# M30517_TX_V1_0.net
KiCad netlist of a schematic drawn in Altium Designer
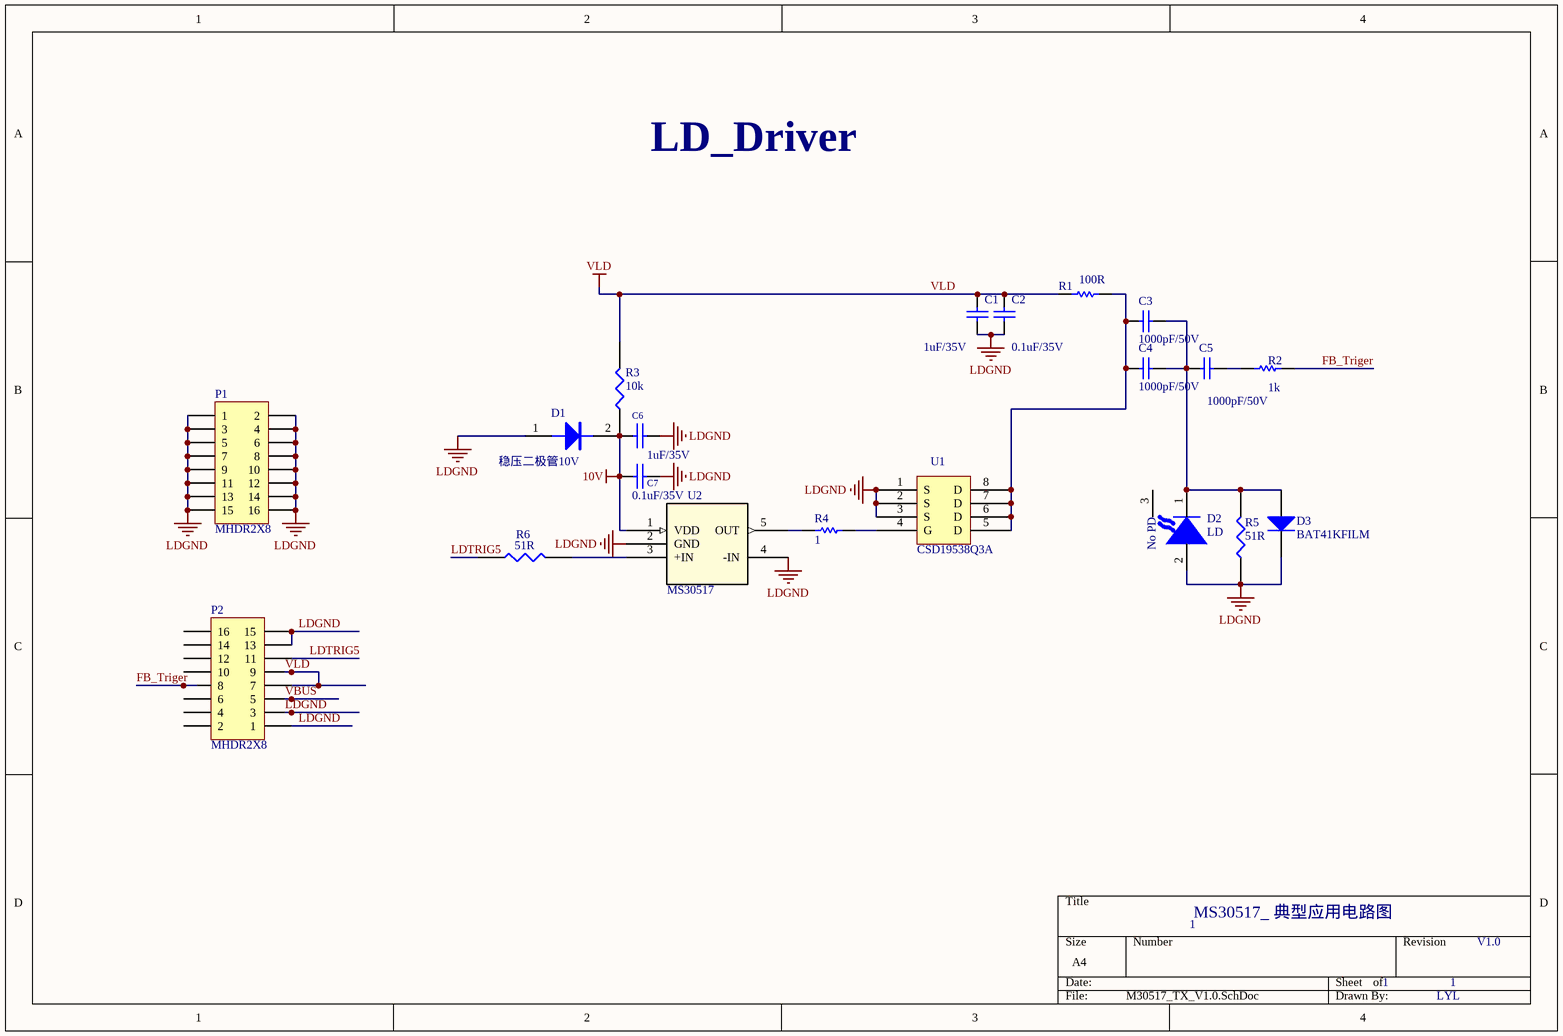
[diagram p0: M30517_TX_V1.0.SchDoc]

(export (version "E")
  (design (tool "Eeschema 10.0.6"))
  (components
    (comp (ref "C1")
      (value "1uF/35V")
      (footprint "C 0603_L")
      (description "Walsin - 1uF, 50V, X5R, 10%")
      (fields (field (name "Comment") "0603X105K500CT") (field (name "PUBLISHER") "Altium Limited"))
      (libsource (lib "Miscellaneous Devices") (part "Cap"))
    )
    (comp (ref "C2")
      (value "0.1uF/35V")
      (footprint "C 0603_L")
      (description "Walsin - 1uF, 50V, X5R, 10%")
      (fields (field (name "Comment") "0603X105K500CT") (field (name "PUBLISHER") "Altium Limited"))
      (libsource (lib "Miscellaneous Devices") (part "Cap"))
    )
    (comp (ref "C3")
      (value "1000pF/50V")
      (footprint "C 0603_L")
      (description "1000pF,  0402 ,50V, NP0, 2%")
      (fields (field (name "Comment") "C0402C331J1GACAUTO") (field (name "PUBLISHER") "Altium Limited"))
      (libsource (lib "Miscellaneous Devices") (part "Cap"))
    )
    (comp (ref "C4")
      (value "1000pF/50V")
      (footprint "C 0603_L")
      (description "1000pF,  0402 ,50V, NP0, 5%")
      (fields (field (name "PUBLISHER") "Altium Limited"))
      (libsource (lib "Miscellaneous Devices") (part "Cap"))
    )
    (comp (ref "C5")
      (value "1000pF/50V")
      (footprint "C 0603_L")
      (description "1000pF,  0402 ,50V, NP0, 2%")
      (fields (field (name "PUBLISHER") "Altium Limited"))
      (libsource (lib "Miscellaneous Devices") (part "Cap"))
    )
    (comp (ref "C6")
      (value "1uF/35V")
      (footprint "C 0603_L")
      (description "Murata - 1nF, 50V, X7R, 10%")
      (fields (field (name "Comment") "GRM155R71H102KA01D"))
      (libsource (lib "*") (part "CAP"))
    )
    (comp (ref "C7")
      (value "0.1uF/35V")
      (footprint "C 0603_L")
      (description "Murata - 0.1uF, 50V, X7R, 10%")
      (fields (field (name "Comment") "(*)GCM155R71H104KE02D"))
      (libsource (lib "*") (part "CAP"))
    )
    (comp (ref "D1")
      (value "稳压二极管10V")
      (footprint "SOD-323")
      (description "Diode")
      (libsource (lib "*") (part "DIODE"))
    )
    (comp (ref "D2")
      (value "LD")
      (footprint "LD1")
      (description "Laser")
      (libsource (lib "Myschpassive") (part "LD_Cathode_NOPD"))
    )
    (comp (ref "D3")
      (value "BAT41KFILM")
      (footprint "SOD-523")
      (description "STM - Sckottky, 200mA, 100 V")
      (fields (field (name "PUBLISHER") "Altium Limited"))
      (libsource (lib "Miscellaneous Devices") (part "Diode"))
    )
    (comp (ref "P1")
      (value "MHDR2X8")
      (footprint "HDR2.54-M-LS-2x8P")
      (description "Header, 8-Pin, Dual row")
      (fields (field (name "PUBLISHER") "Altium Limited"))
      (libsource (lib "Miscellaneous Connectors") (part "MHDR2X8"))
    )
    (comp (ref "P2")
      (value "MHDR2X8")
      (footprint "HDR2.54-M-LS-2x8P")
      (description "Header, 8-Pin, Dual row")
      (fields (field (name "PUBLISHER") "Altium Limited"))
      (libsource (lib "") (part "MHDR2X8_1"))
    )
    (comp (ref "R1")
      (value "100R")
      (footprint "0603R")
      (description "Yageo - 1K, 1/8W, 1 %")
      (fields (field (name "PUBLISHER") "Altium Limited"))
      (libsource (lib "Miscellaneous Devices") (part "Res1"))
    )
    (comp (ref "R2")
      (value "1k")
      (footprint "0603R")
      (description "Yageo - 1K, 1/8W, 1 %")
      (fields (field (name "Comment") "RC0402FR-7W1KL") (field (name "PUBLISHER") "Altium Limited"))
      (libsource (lib "Miscellaneous Devices") (part "Res1"))
    )
    (comp (ref "R3") (value "10k") (footprint "0603R") (libsource (lib "*") (part "RES1")))
    (comp (ref "R4")
      (value "1")
      (footprint "0603R")
      (description "10ohm, 0402,1/16W, 1 %")
      (fields (field (name "Comment") "CR0402F10RQ10") (field (name "PUBLISHER") "Altium Limited"))
      (libsource (lib "Miscellaneous Devices") (part "Res1"))
    )
    (comp (ref "R5") (value "51R") (footprint "0603R") (libsource (lib "*") (part "RES1")))
    (comp (ref "R6") (value "51R") (footprint "0603R") (libsource (lib "*") (part "RES1")))
    (comp (ref "U1") (value "CSD19538Q3A") (footprint "QA3") (libsource (lib "Schlib2") (part "N_MOSFET")))
    (comp (ref "U2")
      (value "MS30517")
      (footprint "SOT23-5")
      (description "UCC27157")
      (fields
        (field (name "MANUFACTURER_PART_NUMBER") "MCP9501PT-115E/OT")
        (field (name "COPYRIGHT") "Copyright (C) 2018 Accelerated Designs. All rights reserved")
      )
      (libsource (lib "schlib") (part "UC27517A"))
    )
  )
  (nets
    (net (code "1") (name "/FB_Triger") (class "Default")
      (node (ref "P2") (pin "8") (pinfunction "8_8") (pintype "passive"))
      (node (ref "R2") (pin "1") (pinfunction "1_1") (pintype "passive"))
    )
    (net (code "2") (name "/LDTRIG5") (class "Default")
      (node (ref "P2") (pin "11") (pinfunction "11_11") (pintype "passive"))
      (node (ref "R6") (pin "1") (pinfunction "1_1") (pintype "passive"))
    )
    (net (code "3") (name "/VBUS") (class "Default")
      (node (ref "P2") (pin "5") (pinfunction "5_5") (pintype "passive"))
    )
    (net (code "4") (name "10V") (class "Default")
      (node (ref "C6") (pin "2") (pinfunction "2_2") (pintype "passive"))
      (node (ref "C7") (pin "2") (pinfunction "2_2") (pintype "passive"))
      (node (ref "D1") (pin "2") (pinfunction "K_2") (pintype "passive"))
      (node (ref "R3") (pin "1") (pinfunction "1_1") (pintype "passive"))
      (node (ref "U2") (pin "1") (pinfunction "VDD_1") (pintype "input"))
    )
    (net (code "5") (name "LDGND") (class "Default")
      (node (ref "C1") (pin "2") (pinfunction "2_2") (pintype "passive"))
      (node (ref "C2") (pin "2") (pinfunction "2_2") (pintype "passive"))
      (node (ref "C6") (pin "1") (pinfunction "1_1") (pintype "passive"))
      (node (ref "C7") (pin "1") (pinfunction "1_1") (pintype "passive"))
      (node (ref "D1") (pin "1") (pinfunction "A_1") (pintype "passive"))
      (node (ref "D2") (pin "2") (pintype "passive"))
      (node (ref "D3") (pin "2") (pinfunction "K_2") (pintype "passive"))
      (node (ref "P1") (pin "1") (pinfunction "1_1") (pintype "passive"))
      (node (ref "P1") (pin "10") (pinfunction "10_10") (pintype "passive"))
      (node (ref "P1") (pin "11") (pinfunction "11_11") (pintype "passive"))
      (node (ref "P1") (pin "12") (pinfunction "12_12") (pintype "passive"))
      (node (ref "P1") (pin "13") (pinfunction "13_13") (pintype "passive"))
      (node (ref "P1") (pin "14") (pinfunction "14_14") (pintype "passive"))
      (node (ref "P1") (pin "15") (pinfunction "15_15") (pintype "passive"))
      (node (ref "P1") (pin "16") (pinfunction "16_16") (pintype "passive"))
      (node (ref "P1") (pin "2") (pinfunction "2_2") (pintype "passive"))
      (node (ref "P1") (pin "3") (pinfunction "3_3") (pintype "passive"))
      (node (ref "P1") (pin "4") (pinfunction "4_4") (pintype "passive"))
      (node (ref "P1") (pin "5") (pinfunction "5_5") (pintype "passive"))
      (node (ref "P1") (pin "6") (pinfunction "6_6") (pintype "passive"))
      (node (ref "P1") (pin "7") (pinfunction "7_7") (pintype "passive"))
      (node (ref "P1") (pin "8") (pinfunction "8_8") (pintype "passive"))
      (node (ref "P1") (pin "9") (pinfunction "9_9") (pintype "passive"))
      (node (ref "P2") (pin "1") (pinfunction "1_1") (pintype "passive"))
      (node (ref "P2") (pin "13") (pinfunction "13_13") (pintype "passive"))
      (node (ref "P2") (pin "15") (pinfunction "15_15") (pintype "passive"))
      (node (ref "P2") (pin "3") (pinfunction "3_3") (pintype "passive"))
      (node (ref "R5") (pin "1") (pinfunction "1_1") (pintype "passive"))
      (node (ref "U1") (pin "1") (pinfunction "S_1") (pintype "passive"))
      (node (ref "U1") (pin "2") (pinfunction "S_2") (pintype "passive"))
      (node (ref "U1") (pin "3") (pinfunction "S_3") (pintype "passive"))
      (node (ref "U2") (pin "2") (pinfunction "GND_2") (pintype "power_in"))
      (node (ref "U2") (pin "4") (pinfunction "-IN_4") (pintype "power_in"))
    )
    (net (code "6") (name "Net-(C3-Pad1)") (class "Default")
      (node (ref "C3") (pin "1") (pinfunction "1_1") (pintype "passive"))
      (node (ref "C4") (pin "1") (pinfunction "1_1") (pintype "passive"))
      (node (ref "R1") (pin "1") (pinfunction "1_1") (pintype "passive"))
      (node (ref "U1") (pin "5") (pinfunction "D_5") (pintype "passive"))
      (node (ref "U1") (pin "6") (pinfunction "D_6") (pintype "passive"))
      (node (ref "U1") (pin "7") (pinfunction "D_7") (pintype "passive"))
      (node (ref "U1") (pin "8") (pinfunction "D_8") (pintype "passive"))
    )
    (net (code "7") (name "Net-(C5-Pad2)") (class "Default")
      (node (ref "C5") (pin "2") (pinfunction "2_2") (pintype "passive"))
      (node (ref "R2") (pin "2") (pinfunction "2_2") (pintype "passive"))
    )
    (net (code "8") (name "Net-(D3-A)") (class "Default")
      (node (ref "C3") (pin "2") (pinfunction "2_2") (pintype "passive"))
      (node (ref "C4") (pin "2") (pinfunction "2_2") (pintype "passive"))
      (node (ref "C5") (pin "1") (pinfunction "1_1") (pintype "passive"))
      (node (ref "D2") (pin "1") (pintype "passive"))
      (node (ref "D3") (pin "1") (pinfunction "A_1") (pintype "passive"))
      (node (ref "R5") (pin "2") (pinfunction "2_2") (pintype "passive"))
    )
    (net (code "9") (name "Net-(U1-G)") (class "Default")
      (node (ref "R4") (pin "1") (pinfunction "1_1") (pintype "passive"))
      (node (ref "U1") (pin "4") (pinfunction "G_4") (pintype "passive"))
    )
    (net (code "10") (name "Net-(U2-+IN)") (class "Default")
      (node (ref "R6") (pin "2") (pinfunction "2_2") (pintype "passive"))
      (node (ref "U2") (pin "3") (pinfunction "+IN_3") (pintype "passive"))
    )
    (net (code "11") (name "Net-(U2-OUT)") (class "Default")
      (node (ref "R4") (pin "2") (pinfunction "2_2") (pintype "passive"))
      (node (ref "U2") (pin "5") (pinfunction "OUT_5") (pintype "output"))
    )
    (net (code "12") (name "VLD") (class "Default")
      (node (ref "C1") (pin "1") (pinfunction "1_1") (pintype "passive"))
      (node (ref "C2") (pin "1") (pinfunction "1_1") (pintype "passive"))
      (node (ref "P2") (pin "7") (pinfunction "7_7") (pintype "passive"))
      (node (ref "P2") (pin "9") (pinfunction "9_9") (pintype "passive"))
      (node (ref "R1") (pin "2") (pinfunction "2_2") (pintype "passive"))
      (node (ref "R3") (pin "2") (pinfunction "2_2") (pintype "passive"))
    )
    (net (code "13") (name "unconnected-(D2-Pad3)") (class "Default")
      (node (ref "D2") (pin "3") (pintype "passive"))
    )
    (net (code "14") (name "unconnected-(P2-Pad2)") (class "Default")
      (node (ref "P2") (pin "2") (pinfunction "2_2") (pintype "passive"))
    )
    (net (code "15") (name "unconnected-(P2-Pad4)") (class "Default")
      (node (ref "P2") (pin "4") (pinfunction "4_4") (pintype "passive"))
    )
    (net (code "16") (name "unconnected-(P2-Pad6)") (class "Default")
      (node (ref "P2") (pin "6") (pinfunction "6_6") (pintype "passive"))
    )
    (net (code "17") (name "unconnected-(P2-Pad10)") (class "Default")
      (node (ref "P2") (pin "10") (pinfunction "10_10") (pintype "passive"))
    )
    (net (code "18") (name "unconnected-(P2-Pad12)") (class "Default")
      (node (ref "P2") (pin "12") (pinfunction "12_12") (pintype "passive"))
    )
    (net (code "19") (name "unconnected-(P2-Pad14)") (class "Default")
      (node (ref "P2") (pin "14") (pinfunction "14_14") (pintype "passive"))
    )
    (net (code "20") (name "unconnected-(P2-Pad16)") (class "Default")
      (node (ref "P2") (pin "16") (pinfunction "16_16") (pintype "passive"))
    )
  )
)
